# eeprom.net
KiCad netlist of a schematic drawn in Altium Designer
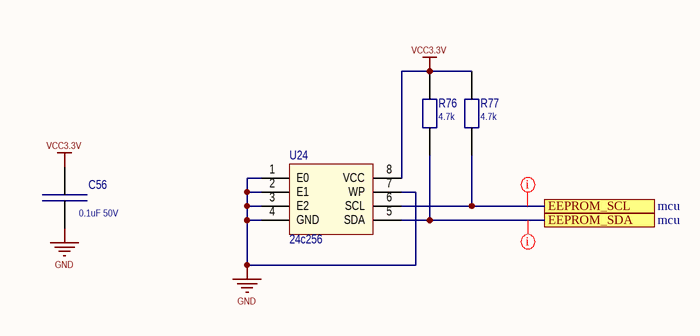
[diagram p0: eeprom.SchDoc]

(export (version "E")
  (design (tool "Eeschema 10.0.6"))
  (components
    (comp (ref "C56")
      (value "0.1uF 50V")
      (footprint "C_0603")
      (description "Capacitor")
      (fields (field (name "PART") "CC0603KPX7R9BB104") (field (name "JLCPCB PART") "C14663"))
      (libsource (lib "AX_Altium_v2.3") (part "C0603"))
    )
    (comp (ref "R76")
      (value "4.7k")
      (footprint "R_0603")
      (description "Resistor")
      (fields (field (name "PART") "RC0603FR-074K7L") (field (name "JLCPCB PART") "C99782"))
      (libsource (lib "resistors") (part "RES_SMD"))
    )
    (comp (ref "R77")
      (value "4.7k")
      (footprint "R_0603")
      (description "Resistor")
      (fields (field (name "PART") "RC0603FR-074K7L") (field (name "JLCPCB PART") "C99782"))
      (libsource (lib "resistors") (part "RES_SMD"))
    )
    (comp (ref "U24")
      (value "24c256")
      (footprint "SO-8_M")
      (description "256-Kbit I2C-compatible Serial EEPROM")
      (fields (field (name "PART") "AT24C256C") (field (name "JLCPCB PART") "C6482"))
      (libsource (lib "discret_ic") (part "24c256"))
    )
  )
  (nets
    (net (code "1") (name "/EEPROM_SCL") (class "Default")
      (node (ref "R77") (pin "1") (pinfunction "1_1") (pintype "passive"))
      (node (ref "U24") (pin "6") (pinfunction "SCL_6") (pintype "passive"))
    )
    (net (code "2") (name "/EEPROM_SDA") (class "Default")
      (node (ref "R76") (pin "1") (pinfunction "1_1") (pintype "passive"))
      (node (ref "U24") (pin "5") (pinfunction "SDA_5") (pintype "passive"))
    )
    (net (code "3") (name "GND") (class "Default")
      (node (ref "C56") (pin "1") (pinfunction "1_1") (pintype "passive"))
      (node (ref "U24") (pin "1") (pinfunction "E0_1") (pintype "passive"))
      (node (ref "U24") (pin "2") (pinfunction "E1_2") (pintype "passive"))
      (node (ref "U24") (pin "3") (pinfunction "E2_3") (pintype "passive"))
      (node (ref "U24") (pin "4") (pinfunction "GND_4") (pintype "passive"))
      (node (ref "U24") (pin "7") (pinfunction "WP_7") (pintype "passive"))
    )
    (net (code "4") (name "VCC3.3V") (class "Default")
      (node (ref "C56") (pin "2") (pinfunction "2_2") (pintype "passive"))
      (node (ref "R76") (pin "2") (pinfunction "2_2") (pintype "passive"))
      (node (ref "R77") (pin "2") (pinfunction "2_2") (pintype "passive"))
      (node (ref "U24") (pin "8") (pinfunction "VCC_8") (pintype "passive"))
    )
  )
)
